# USB2LPT_1_7_adapter.net
KiCad netlist of a schematic drawn in EAGLE
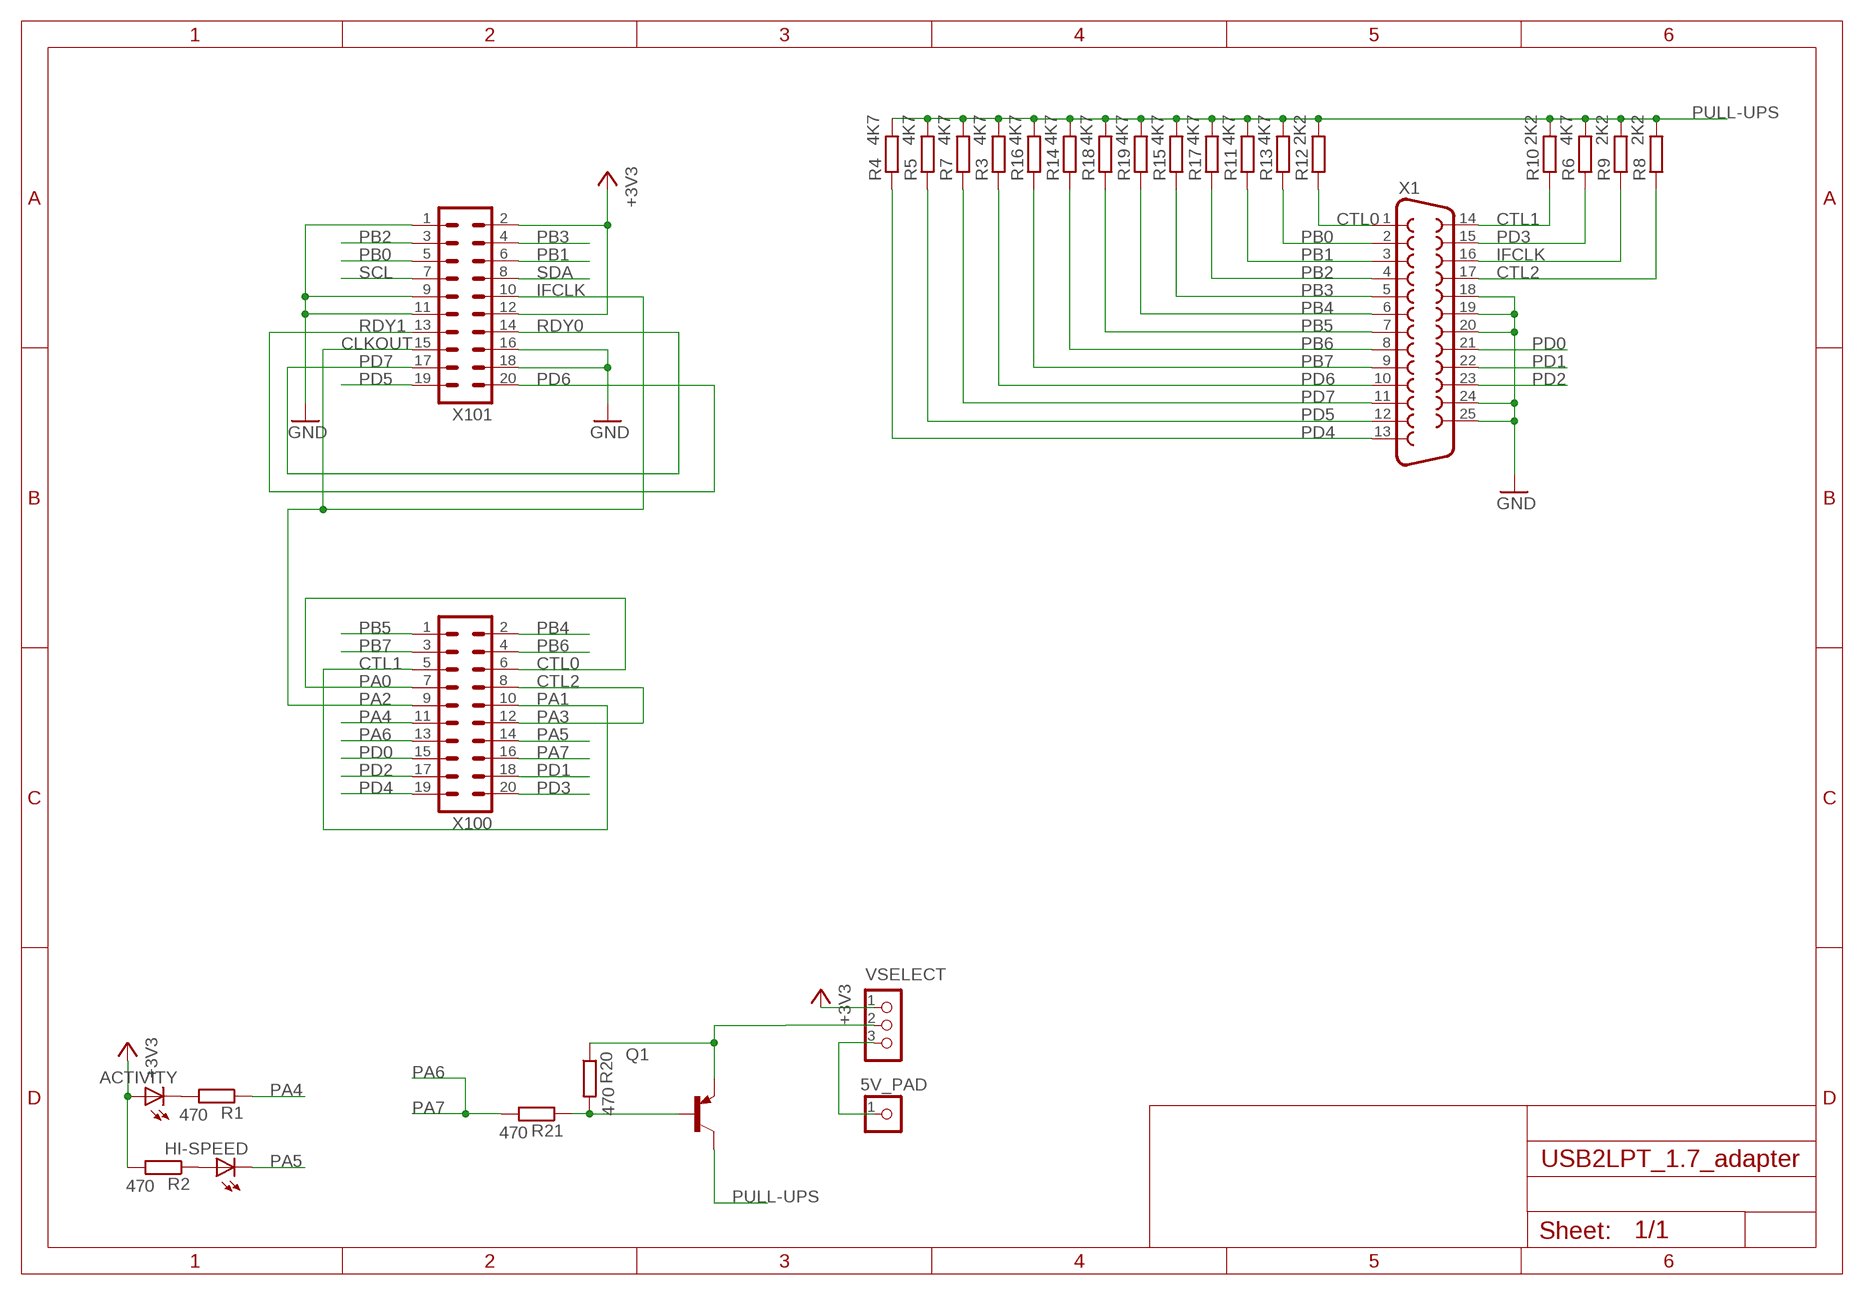
[diagram p0: schematic, sheet 1]

(export (version "E")
  (design (tool "Eeschema 10.0.6"))
  (components
    (comp (ref "+5V")
      (value "CON_HEADER_1X01-PTH_08_17")
      (footprint "eagle-import:M1X2_08_17")
      (libsource (lib "eagle-import") (part "CON_HEADER_1X01-PTH_08_17"))
    )
    (comp (ref "ACTIVITY")
      (value "LED-0805")
      (footprint "eagle-import:LED-805")
      (libsource (lib "eagle-import") (part "LED-0805"))
    )
    (comp (ref "HI-SPEED")
      (value "LED-0805")
      (footprint "eagle-import:LED-805")
      (libsource (lib "eagle-import") (part "LED-0805"))
    )
    (comp (ref "Q1")
      (value "TRANSISTOR_BJT_PNP-SOT-23-BEC")
      (footprint "eagle-import:SOT-23")
      (libsource (lib "eagle-import") (part "TRANSISTOR_BJT_PNP-SOT-23-BEC"))
    )
    (comp (ref "R1")
      (value "470")
      (footprint "eagle-import:R805")
      (libsource (lib "eagle-import") (part "RESISTOR-0805R805"))
    )
    (comp (ref "R2")
      (value "470")
      (footprint "eagle-import:R805")
      (libsource (lib "eagle-import") (part "RESISTOR-0805R805"))
    )
    (comp (ref "R3")
      (value "4K7")
      (footprint "eagle-import:R805")
      (libsource (lib "eagle-import") (part "RESISTOR-0805R805"))
    )
    (comp (ref "R4")
      (value "4K7")
      (footprint "eagle-import:R805")
      (libsource (lib "eagle-import") (part "RESISTOR-0805R805"))
    )
    (comp (ref "R5")
      (value "4K7")
      (footprint "eagle-import:R805")
      (libsource (lib "eagle-import") (part "RESISTOR-0805R805"))
    )
    (comp (ref "R6")
      (value "4K7")
      (footprint "eagle-import:R805")
      (libsource (lib "eagle-import") (part "RESISTOR-0805R805"))
    )
    (comp (ref "R7")
      (value "4K7")
      (footprint "eagle-import:R805")
      (libsource (lib "eagle-import") (part "RESISTOR-0805R805"))
    )
    (comp (ref "R8")
      (value "2K2")
      (footprint "eagle-import:R805")
      (libsource (lib "eagle-import") (part "RESISTOR-0805R805"))
    )
    (comp (ref "R9")
      (value "2K2")
      (footprint "eagle-import:R805")
      (libsource (lib "eagle-import") (part "RESISTOR-0805R805"))
    )
    (comp (ref "R10")
      (value "2K2")
      (footprint "eagle-import:R805")
      (libsource (lib "eagle-import") (part "RESISTOR-0805R805"))
    )
    (comp (ref "R11")
      (value "4K7")
      (footprint "eagle-import:R805")
      (libsource (lib "eagle-import") (part "RESISTOR-0805R805"))
    )
    (comp (ref "R12")
      (value "2K2")
      (footprint "eagle-import:R805")
      (libsource (lib "eagle-import") (part "RESISTOR-0805R805"))
    )
    (comp (ref "R13")
      (value "4K7")
      (footprint "eagle-import:R805")
      (libsource (lib "eagle-import") (part "RESISTOR-0805R805"))
    )
    (comp (ref "R14")
      (value "4K7")
      (footprint "eagle-import:R805")
      (libsource (lib "eagle-import") (part "RESISTOR-0805R805"))
    )
    (comp (ref "R15")
      (value "4K7")
      (footprint "eagle-import:R805")
      (libsource (lib "eagle-import") (part "RESISTOR-0805R805"))
    )
    (comp (ref "R16")
      (value "4K7")
      (footprint "eagle-import:R805")
      (libsource (lib "eagle-import") (part "RESISTOR-0805R805"))
    )
    (comp (ref "R17")
      (value "4K7")
      (footprint "eagle-import:R805")
      (libsource (lib "eagle-import") (part "RESISTOR-0805R805"))
    )
    (comp (ref "R18")
      (value "4K7")
      (footprint "eagle-import:R805")
      (libsource (lib "eagle-import") (part "RESISTOR-0805R805"))
    )
    (comp (ref "R19")
      (value "4K7")
      (footprint "eagle-import:R805")
      (libsource (lib "eagle-import") (part "RESISTOR-0805R805"))
    )
    (comp (ref "R20")
      (value "470")
      (footprint "eagle-import:R805")
      (libsource (lib "eagle-import") (part "RESISTOR-0805R805"))
    )
    (comp (ref "R21")
      (value "470")
      (footprint "eagle-import:R805")
      (libsource (lib "eagle-import") (part "RESISTOR-0805R805"))
    )
    (comp (ref "VSELECT")
      (value "VSELECT_HEADER")
      (footprint "eagle-import:HEADER_1X3")
      (libsource (lib "eagle-import") (part "VSELECT_HEADER"))
    )
    (comp (ref "X1")
      (value "F25D")
      (footprint "eagle-import:F25D")
      (libsource (lib "eagle-import") (part "F25D"))
    )
    (comp (ref "X100")
      (value "MA10-2")
      (footprint "eagle-import:MA10-2")
      (libsource (lib "eagle-import") (part "MA10-2"))
    )
    (comp (ref "X101")
      (value "MA10-2")
      (footprint "eagle-import:MA10-2")
      (libsource (lib "eagle-import") (part "MA10-2"))
    )
  )
  (nets
    (net (code "1") (name "+3V3") (class "Default")
      (node (ref "ACTIVITY") (pin "A") (pinfunction "A_A") (pintype "passive"))
      (node (ref "R2") (pin "2") (pinfunction "2_2") (pintype "passive"))
      (node (ref "VSELECT") (pin "1") (pinfunction "1_1") (pintype "bidirectional"))
      (node (ref "X101") (pin "12") (pinfunction "12_12") (pintype "passive"))
      (node (ref "X101") (pin "2") (pinfunction "2_2") (pintype "passive"))
    )
    (net (code "2") (name "/5V_PAD") (class "Default")
      (node (ref "+5V") (pin "1") (pinfunction "1_1") (pintype "passive"))
      (node (ref "VSELECT") (pin "3") (pinfunction "3_3") (pintype "bidirectional"))
    )
    (net (code "3") (name "/CTL0") (class "Default")
      (node (ref "R12") (pin "1") (pinfunction "1_1") (pintype "passive"))
      (node (ref "X1") (pin "1") (pinfunction "1_1") (pintype "passive"))
      (node (ref "X100") (pin "6") (pinfunction "6_6") (pintype "passive"))
      (node (ref "X100") (pin "7") (pinfunction "7_7") (pintype "passive"))
    )
    (net (code "4") (name "/CTL1") (class "Default")
      (node (ref "R10") (pin "1") (pinfunction "1_1") (pintype "passive"))
      (node (ref "X1") (pin "14") (pinfunction "14_14") (pintype "passive"))
      (node (ref "X100") (pin "10") (pinfunction "10_10") (pintype "passive"))
      (node (ref "X100") (pin "5") (pinfunction "5_5") (pintype "passive"))
    )
    (net (code "5") (name "/CTL2") (class "Default")
      (node (ref "R8") (pin "1") (pinfunction "1_1") (pintype "passive"))
      (node (ref "X1") (pin "17") (pinfunction "17_17") (pintype "passive"))
      (node (ref "X100") (pin "12") (pinfunction "12_12") (pintype "passive"))
      (node (ref "X100") (pin "8") (pinfunction "8_8") (pintype "passive"))
    )
    (net (code "6") (name "/IFCLK") (class "Default")
      (node (ref "R9") (pin "1") (pinfunction "1_1") (pintype "passive"))
      (node (ref "X1") (pin "16") (pinfunction "16_16") (pintype "passive"))
      (node (ref "X100") (pin "9") (pinfunction "9_9") (pintype "passive"))
      (node (ref "X101") (pin "10") (pinfunction "10_10") (pintype "passive"))
      (node (ref "X101") (pin "15") (pinfunction "15_15") (pintype "passive"))
    )
    (net (code "7") (name "/PA4") (class "Default")
      (node (ref "R1") (pin "1") (pinfunction "1_1") (pintype "passive"))
      (node (ref "X100") (pin "11") (pinfunction "11_11") (pintype "passive"))
    )
    (net (code "8") (name "/PA5") (class "Default")
      (node (ref "HI-SPEED") (pin "C") (pinfunction "C_C") (pintype "passive"))
      (node (ref "X100") (pin "14") (pinfunction "14_14") (pintype "passive"))
    )
    (net (code "9") (name "/PA6") (class "Default")
      (node (ref "R21") (pin "2") (pinfunction "2_2") (pintype "passive"))
      (node (ref "X100") (pin "13") (pinfunction "13_13") (pintype "passive"))
      (node (ref "X100") (pin "16") (pinfunction "16_16") (pintype "passive"))
    )
    (net (code "10") (name "/PB0") (class "Default")
      (node (ref "R13") (pin "1") (pinfunction "1_1") (pintype "passive"))
      (node (ref "X1") (pin "2") (pinfunction "2_2") (pintype "passive"))
      (node (ref "X101") (pin "5") (pinfunction "5_5") (pintype "passive"))
    )
    (net (code "11") (name "/PB1") (class "Default")
      (node (ref "R11") (pin "1") (pinfunction "1_1") (pintype "passive"))
      (node (ref "X1") (pin "3") (pinfunction "3_3") (pintype "passive"))
      (node (ref "X101") (pin "6") (pinfunction "6_6") (pintype "passive"))
    )
    (net (code "12") (name "/PB2") (class "Default")
      (node (ref "R17") (pin "1") (pinfunction "1_1") (pintype "passive"))
      (node (ref "X1") (pin "4") (pinfunction "4_4") (pintype "passive"))
      (node (ref "X101") (pin "3") (pinfunction "3_3") (pintype "passive"))
    )
    (net (code "13") (name "/PB3") (class "Default")
      (node (ref "R15") (pin "1") (pinfunction "1_1") (pintype "passive"))
      (node (ref "X1") (pin "5") (pinfunction "5_5") (pintype "passive"))
      (node (ref "X101") (pin "4") (pinfunction "4_4") (pintype "passive"))
    )
    (net (code "14") (name "/PB4") (class "Default")
      (node (ref "R19") (pin "1") (pinfunction "1_1") (pintype "passive"))
      (node (ref "X1") (pin "6") (pinfunction "6_6") (pintype "passive"))
      (node (ref "X100") (pin "2") (pinfunction "2_2") (pintype "passive"))
    )
    (net (code "15") (name "/PB5") (class "Default")
      (node (ref "R18") (pin "1") (pinfunction "1_1") (pintype "passive"))
      (node (ref "X1") (pin "7") (pinfunction "7_7") (pintype "passive"))
      (node (ref "X100") (pin "1") (pinfunction "1_1") (pintype "passive"))
    )
    (net (code "16") (name "/PB6") (class "Default")
      (node (ref "R14") (pin "1") (pinfunction "1_1") (pintype "passive"))
      (node (ref "X1") (pin "8") (pinfunction "8_8") (pintype "passive"))
      (node (ref "X100") (pin "4") (pinfunction "4_4") (pintype "passive"))
    )
    (net (code "17") (name "/PB7") (class "Default")
      (node (ref "R16") (pin "1") (pinfunction "1_1") (pintype "passive"))
      (node (ref "X1") (pin "9") (pinfunction "9_9") (pintype "passive"))
      (node (ref "X100") (pin "3") (pinfunction "3_3") (pintype "passive"))
    )
    (net (code "18") (name "/PD0") (class "Default")
      (node (ref "X1") (pin "21") (pinfunction "21_21") (pintype "passive"))
      (node (ref "X100") (pin "15") (pinfunction "15_15") (pintype "passive"))
    )
    (net (code "19") (name "/PD1") (class "Default")
      (node (ref "X1") (pin "22") (pinfunction "22_22") (pintype "passive"))
      (node (ref "X100") (pin "18") (pinfunction "18_18") (pintype "passive"))
    )
    (net (code "20") (name "/PD2") (class "Default")
      (node (ref "X1") (pin "23") (pinfunction "23_23") (pintype "passive"))
      (node (ref "X100") (pin "17") (pinfunction "17_17") (pintype "passive"))
    )
    (net (code "21") (name "/PD3") (class "Default")
      (node (ref "R6") (pin "1") (pinfunction "1_1") (pintype "passive"))
      (node (ref "X1") (pin "15") (pinfunction "15_15") (pintype "passive"))
      (node (ref "X100") (pin "20") (pinfunction "20_20") (pintype "passive"))
    )
    (net (code "22") (name "/PD4") (class "Default")
      (node (ref "R4") (pin "1") (pinfunction "1_1") (pintype "passive"))
      (node (ref "X1") (pin "13") (pinfunction "13_13") (pintype "passive"))
      (node (ref "X100") (pin "19") (pinfunction "19_19") (pintype "passive"))
    )
    (net (code "23") (name "/PD5") (class "Default")
      (node (ref "R5") (pin "1") (pinfunction "1_1") (pintype "passive"))
      (node (ref "X1") (pin "12") (pinfunction "12_12") (pintype "passive"))
      (node (ref "X101") (pin "19") (pinfunction "19_19") (pintype "passive"))
    )
    (net (code "24") (name "/PD6") (class "Default")
      (node (ref "R3") (pin "1") (pinfunction "1_1") (pintype "passive"))
      (node (ref "X1") (pin "10") (pinfunction "10_10") (pintype "passive"))
      (node (ref "X101") (pin "13") (pinfunction "13_13") (pintype "passive"))
      (node (ref "X101") (pin "20") (pinfunction "20_20") (pintype "passive"))
    )
    (net (code "25") (name "/PD7") (class "Default")
      (node (ref "R7") (pin "1") (pinfunction "1_1") (pintype "passive"))
      (node (ref "X1") (pin "11") (pinfunction "11_11") (pintype "passive"))
      (node (ref "X101") (pin "14") (pinfunction "14_14") (pintype "passive"))
      (node (ref "X101") (pin "17") (pinfunction "17_17") (pintype "passive"))
    )
    (net (code "26") (name "/PULL-UPS") (class "Default")
      (node (ref "Q1") (pin "3") (pinfunction "C_3") (pintype "passive"))
      (node (ref "R10") (pin "2") (pinfunction "2_2") (pintype "passive"))
      (node (ref "R11") (pin "2") (pinfunction "2_2") (pintype "passive"))
      (node (ref "R12") (pin "2") (pinfunction "2_2") (pintype "passive"))
      (node (ref "R13") (pin "2") (pinfunction "2_2") (pintype "passive"))
      (node (ref "R14") (pin "2") (pinfunction "2_2") (pintype "passive"))
      (node (ref "R15") (pin "2") (pinfunction "2_2") (pintype "passive"))
      (node (ref "R16") (pin "2") (pinfunction "2_2") (pintype "passive"))
      (node (ref "R17") (pin "2") (pinfunction "2_2") (pintype "passive"))
      (node (ref "R18") (pin "2") (pinfunction "2_2") (pintype "passive"))
      (node (ref "R19") (pin "2") (pinfunction "2_2") (pintype "passive"))
      (node (ref "R3") (pin "2") (pinfunction "2_2") (pintype "passive"))
      (node (ref "R4") (pin "2") (pinfunction "2_2") (pintype "passive"))
      (node (ref "R5") (pin "2") (pinfunction "2_2") (pintype "passive"))
      (node (ref "R6") (pin "2") (pinfunction "2_2") (pintype "passive"))
      (node (ref "R7") (pin "2") (pinfunction "2_2") (pintype "passive"))
      (node (ref "R8") (pin "2") (pinfunction "2_2") (pintype "passive"))
      (node (ref "R9") (pin "2") (pinfunction "2_2") (pintype "passive"))
    )
    (net (code "27") (name "/SCL") (class "Default")
      (node (ref "X101") (pin "7") (pinfunction "7_7") (pintype "passive"))
    )
    (net (code "28") (name "/SDA") (class "Default")
      (node (ref "X101") (pin "8") (pinfunction "8_8") (pintype "passive"))
    )
    (net (code "29") (name "/VSELECT") (class "Default")
      (node (ref "Q1") (pin "2") (pinfunction "E_2") (pintype "passive"))
      (node (ref "R20") (pin "1") (pinfunction "1_1") (pintype "passive"))
      (node (ref "VSELECT") (pin "2") (pinfunction "2_2") (pintype "bidirectional"))
    )
    (net (code "30") (name "GND") (class "Default")
      (node (ref "X1") (pin "18") (pinfunction "18_18") (pintype "passive"))
      (node (ref "X1") (pin "19") (pinfunction "19_19") (pintype "passive"))
      (node (ref "X1") (pin "20") (pinfunction "20_20") (pintype "passive"))
      (node (ref "X1") (pin "24") (pinfunction "24_24") (pintype "passive"))
      (node (ref "X1") (pin "25") (pinfunction "25_25") (pintype "passive"))
      (node (ref "X101") (pin "1") (pinfunction "1_1") (pintype "passive"))
      (node (ref "X101") (pin "11") (pinfunction "11_11") (pintype "passive"))
      (node (ref "X101") (pin "16") (pinfunction "16_16") (pintype "passive"))
      (node (ref "X101") (pin "18") (pinfunction "18_18") (pintype "passive"))
      (node (ref "X101") (pin "9") (pinfunction "9_9") (pintype "passive"))
    )
    (net (code "31") (name "Net-(ACTIVITY-PadC)") (class "Default")
      (node (ref "ACTIVITY") (pin "C") (pinfunction "C_C") (pintype "passive"))
      (node (ref "R1") (pin "2") (pinfunction "2_2") (pintype "passive"))
    )
    (net (code "32") (name "Net-(HI-SPEED-PadA)") (class "Default")
      (node (ref "HI-SPEED") (pin "A") (pinfunction "A_A") (pintype "passive"))
      (node (ref "R2") (pin "1") (pinfunction "1_1") (pintype "passive"))
    )
    (net (code "33") (name "Net-(Q1-B)") (class "Default")
      (node (ref "Q1") (pin "1") (pinfunction "B_1") (pintype "passive"))
      (node (ref "R20") (pin "2") (pinfunction "2_2") (pintype "passive"))
      (node (ref "R21") (pin "1") (pinfunction "1_1") (pintype "passive"))
    )
  )
)
